# 06-NOTStatusLed.net
KiCad netlist of a schematic drawn in Altium Designer
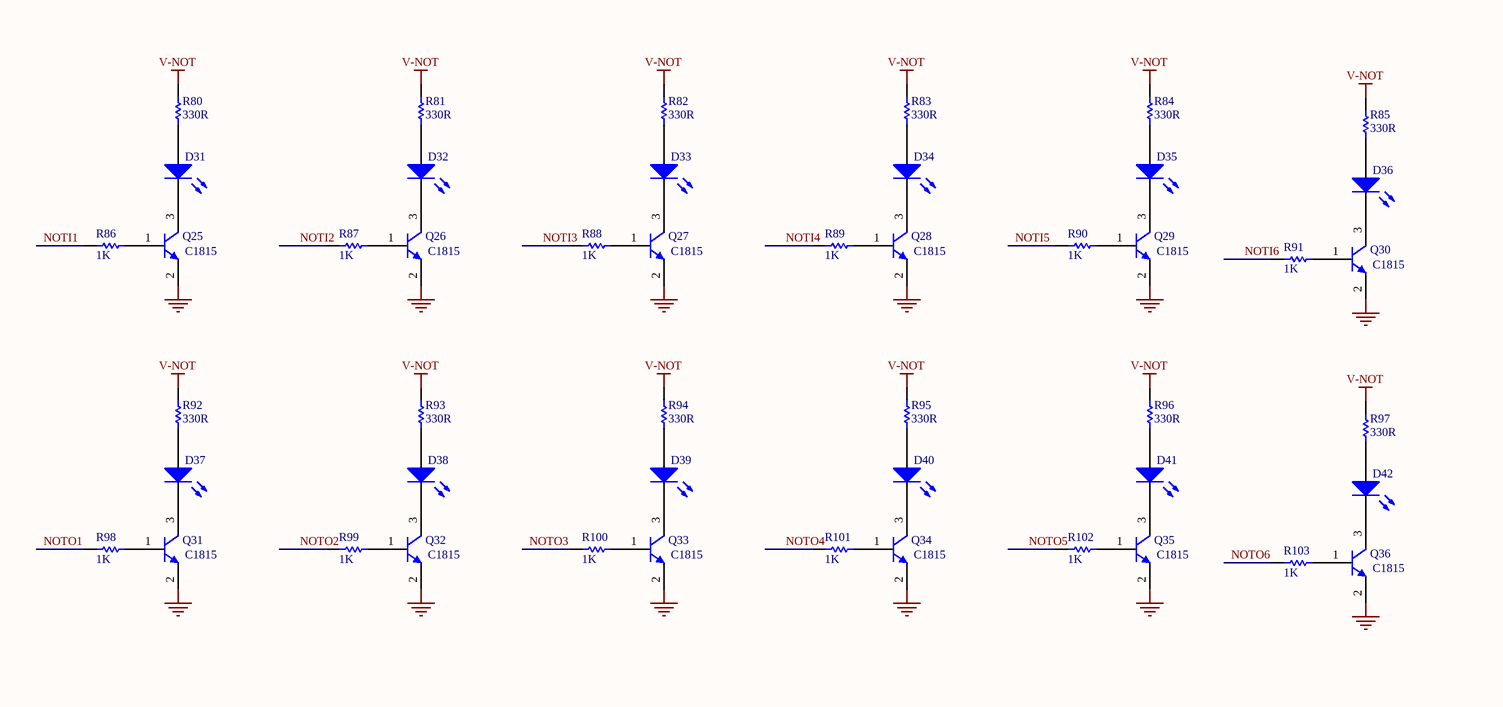
[diagram p0: 06-NOTStatusLed.SchDoc, left]
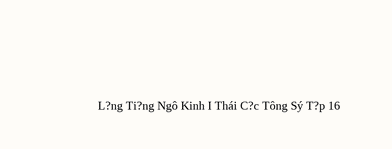
[diagram p1: 06-NOTStatusLed.SchDoc, right]

(export (version "E")
  (design (tool "Eeschema 10.0.6"))
  (components
    (comp (ref "D31")
      (value "LED")
      (footprint "LED-3528")
      (description "Typical RED, GREEN, YELLOW, AMBER GaAs LED")
      (fields (field (name "PUBLISHER") "Altium Limited"))
      (libsource (lib "Miscellaneous Devices") (part "LED2"))
    )
    (comp (ref "D32")
      (value "LED")
      (footprint "LED-3528")
      (description "Typical RED, GREEN, YELLOW, AMBER GaAs LED")
      (fields (field (name "PUBLISHER") "Altium Limited"))
      (libsource (lib "Miscellaneous Devices") (part "LED2"))
    )
    (comp (ref "D33")
      (value "LED")
      (footprint "LED-3528")
      (description "Typical RED, GREEN, YELLOW, AMBER GaAs LED")
      (fields (field (name "PUBLISHER") "Altium Limited"))
      (libsource (lib "Miscellaneous Devices") (part "LED2"))
    )
    (comp (ref "D34")
      (value "LED")
      (footprint "LED-3528")
      (description "Typical RED, GREEN, YELLOW, AMBER GaAs LED")
      (fields (field (name "PUBLISHER") "Altium Limited"))
      (libsource (lib "Miscellaneous Devices") (part "LED2"))
    )
    (comp (ref "D35")
      (value "LED")
      (footprint "LED-3528")
      (description "Typical RED, GREEN, YELLOW, AMBER GaAs LED")
      (fields (field (name "PUBLISHER") "Altium Limited"))
      (libsource (lib "Miscellaneous Devices") (part "LED2"))
    )
    (comp (ref "D36")
      (value "LED")
      (footprint "LED-3528")
      (description "Typical RED, GREEN, YELLOW, AMBER GaAs LED")
      (fields (field (name "PUBLISHER") "Altium Limited"))
      (libsource (lib "Miscellaneous Devices") (part "LED2"))
    )
    (comp (ref "D37")
      (value "LED")
      (footprint "LED-3528")
      (description "Typical RED, GREEN, YELLOW, AMBER GaAs LED")
      (fields (field (name "PUBLISHER") "Altium Limited"))
      (libsource (lib "Miscellaneous Devices") (part "LED2"))
    )
    (comp (ref "D38")
      (value "LED")
      (footprint "LED-3528")
      (description "Typical RED, GREEN, YELLOW, AMBER GaAs LED")
      (fields (field (name "PUBLISHER") "Altium Limited"))
      (libsource (lib "Miscellaneous Devices") (part "LED2"))
    )
    (comp (ref "D39")
      (value "LED")
      (footprint "LED-3528")
      (description "Typical RED, GREEN, YELLOW, AMBER GaAs LED")
      (fields (field (name "PUBLISHER") "Altium Limited"))
      (libsource (lib "Miscellaneous Devices") (part "LED2"))
    )
    (comp (ref "D40")
      (value "LED")
      (footprint "LED-3528")
      (description "Typical RED, GREEN, YELLOW, AMBER GaAs LED")
      (fields (field (name "PUBLISHER") "Altium Limited"))
      (libsource (lib "Miscellaneous Devices") (part "LED2"))
    )
    (comp (ref "D41")
      (value "LED")
      (footprint "LED-3528")
      (description "Typical RED, GREEN, YELLOW, AMBER GaAs LED")
      (fields (field (name "PUBLISHER") "Altium Limited"))
      (libsource (lib "Miscellaneous Devices") (part "LED2"))
    )
    (comp (ref "D42")
      (value "LED")
      (footprint "LED-3528")
      (description "Typical RED, GREEN, YELLOW, AMBER GaAs LED")
      (fields (field (name "PUBLISHER") "Altium Limited"))
      (libsource (lib "Miscellaneous Devices") (part "LED2"))
    )
    (comp (ref "Q25")
      (value "C1815")
      (footprint "SOT23-321")
      (description "NPN Bipolar Transistor")
      (fields (field (name "Comment") "C1815-SMD"))
      (libsource (lib "Miscellaneous Devices") (part "NPN"))
    )
    (comp (ref "Q26")
      (value "C1815")
      (footprint "SOT23-321")
      (description "NPN Bipolar Transistor")
      (fields (field (name "Comment") "C1815-SMD"))
      (libsource (lib "Miscellaneous Devices") (part "NPN"))
    )
    (comp (ref "Q27")
      (value "C1815")
      (footprint "SOT23-321")
      (description "NPN Bipolar Transistor")
      (fields (field (name "Comment") "C1815-SMD"))
      (libsource (lib "Miscellaneous Devices") (part "NPN"))
    )
    (comp (ref "Q28")
      (value "C1815")
      (footprint "SOT23-321")
      (description "NPN Bipolar Transistor")
      (fields (field (name "Comment") "C1815-SMD"))
      (libsource (lib "Miscellaneous Devices") (part "NPN"))
    )
    (comp (ref "Q29")
      (value "C1815")
      (footprint "SOT23-321")
      (description "NPN Bipolar Transistor")
      (fields (field (name "Comment") "C1815-SMD"))
      (libsource (lib "Miscellaneous Devices") (part "NPN"))
    )
    (comp (ref "Q30")
      (value "C1815")
      (footprint "SOT23-321")
      (description "NPN Bipolar Transistor")
      (fields (field (name "Comment") "C1815-SMD"))
      (libsource (lib "Miscellaneous Devices") (part "NPN"))
    )
    (comp (ref "Q31")
      (value "C1815")
      (footprint "SOT23-321")
      (description "NPN Bipolar Transistor")
      (fields (field (name "Comment") "C1815-SMD"))
      (libsource (lib "Miscellaneous Devices") (part "NPN"))
    )
    (comp (ref "Q32")
      (value "C1815")
      (footprint "SOT23-321")
      (description "NPN Bipolar Transistor")
      (fields (field (name "Comment") "C1815-SMD"))
      (libsource (lib "Miscellaneous Devices") (part "NPN"))
    )
    (comp (ref "Q33")
      (value "C1815")
      (footprint "SOT23-321")
      (description "NPN Bipolar Transistor")
      (fields (field (name "Comment") "C1815-SMD"))
      (libsource (lib "Miscellaneous Devices") (part "NPN"))
    )
    (comp (ref "Q34")
      (value "C1815")
      (footprint "SOT23-321")
      (description "NPN Bipolar Transistor")
      (fields (field (name "Comment") "C1815-SMD"))
      (libsource (lib "Miscellaneous Devices") (part "NPN"))
    )
    (comp (ref "Q35")
      (value "C1815")
      (footprint "SOT23-321")
      (description "NPN Bipolar Transistor")
      (fields (field (name "Comment") "C1815-SMD"))
      (libsource (lib "Miscellaneous Devices") (part "NPN"))
    )
    (comp (ref "Q36")
      (value "C1815")
      (footprint "SOT23-321")
      (description "NPN Bipolar Transistor")
      (fields (field (name "Comment") "C1815-SMD"))
      (libsource (lib "Miscellaneous Devices") (part "NPN"))
    )
    (comp (ref "R80")
      (value "330R")
      (footprint "R-0805")
      (description "Resistor")
      (fields (field (name "PUBLISHER") "Altium Limited"))
      (libsource (lib "Miscellaneous Devices") (part "Res1"))
    )
    (comp (ref "R81")
      (value "330R")
      (footprint "R-0805")
      (description "Resistor")
      (fields (field (name "PUBLISHER") "Altium Limited"))
      (libsource (lib "Miscellaneous Devices") (part "Res1"))
    )
    (comp (ref "R82")
      (value "330R")
      (footprint "R-0805")
      (description "Resistor")
      (fields (field (name "PUBLISHER") "Altium Limited"))
      (libsource (lib "Miscellaneous Devices") (part "Res1"))
    )
    (comp (ref "R83")
      (value "330R")
      (footprint "R-0805")
      (description "Resistor")
      (fields (field (name "PUBLISHER") "Altium Limited"))
      (libsource (lib "Miscellaneous Devices") (part "Res1"))
    )
    (comp (ref "R84")
      (value "330R")
      (footprint "R-0805")
      (description "Resistor")
      (fields (field (name "PUBLISHER") "Altium Limited"))
      (libsource (lib "Miscellaneous Devices") (part "Res1"))
    )
    (comp (ref "R85")
      (value "330R")
      (footprint "R-0805")
      (description "Resistor")
      (fields (field (name "PUBLISHER") "Altium Limited"))
      (libsource (lib "Miscellaneous Devices") (part "Res1"))
    )
    (comp (ref "R86")
      (value "1K")
      (footprint "R-0805")
      (description "Resistor")
      (fields (field (name "PUBLISHER") "Altium Limited"))
      (libsource (lib "Miscellaneous Devices") (part "Res1"))
    )
    (comp (ref "R87")
      (value "1K")
      (footprint "R-0805")
      (description "Resistor")
      (fields (field (name "PUBLISHER") "Altium Limited"))
      (libsource (lib "Miscellaneous Devices") (part "Res1"))
    )
    (comp (ref "R88")
      (value "1K")
      (footprint "R-0805")
      (description "Resistor")
      (fields (field (name "PUBLISHER") "Altium Limited"))
      (libsource (lib "Miscellaneous Devices") (part "Res1"))
    )
    (comp (ref "R89")
      (value "1K")
      (footprint "R-0805")
      (description "Resistor")
      (fields (field (name "PUBLISHER") "Altium Limited"))
      (libsource (lib "Miscellaneous Devices") (part "Res1"))
    )
    (comp (ref "R90")
      (value "1K")
      (footprint "R-0805")
      (description "Resistor")
      (fields (field (name "PUBLISHER") "Altium Limited"))
      (libsource (lib "Miscellaneous Devices") (part "Res1"))
    )
    (comp (ref "R91")
      (value "1K")
      (footprint "R-0805")
      (description "Resistor")
      (fields (field (name "PUBLISHER") "Altium Limited"))
      (libsource (lib "Miscellaneous Devices") (part "Res1"))
    )
    (comp (ref "R92")
      (value "330R")
      (footprint "R-0805")
      (description "Resistor")
      (fields (field (name "PUBLISHER") "Altium Limited"))
      (libsource (lib "Miscellaneous Devices") (part "Res1"))
    )
    (comp (ref "R93")
      (value "330R")
      (footprint "R-0805")
      (description "Resistor")
      (fields (field (name "PUBLISHER") "Altium Limited"))
      (libsource (lib "Miscellaneous Devices") (part "Res1"))
    )
    (comp (ref "R94")
      (value "330R")
      (footprint "R-0805")
      (description "Resistor")
      (fields (field (name "PUBLISHER") "Altium Limited"))
      (libsource (lib "Miscellaneous Devices") (part "Res1"))
    )
    (comp (ref "R95")
      (value "330R")
      (footprint "R-0805")
      (description "Resistor")
      (fields (field (name "PUBLISHER") "Altium Limited"))
      (libsource (lib "Miscellaneous Devices") (part "Res1"))
    )
    (comp (ref "R96")
      (value "330R")
      (footprint "R-0805")
      (description "Resistor")
      (fields (field (name "PUBLISHER") "Altium Limited"))
      (libsource (lib "Miscellaneous Devices") (part "Res1"))
    )
    (comp (ref "R97")
      (value "330R")
      (footprint "R-0805")
      (description "Resistor")
      (fields (field (name "PUBLISHER") "Altium Limited"))
      (libsource (lib "Miscellaneous Devices") (part "Res1"))
    )
    (comp (ref "R98")
      (value "1K")
      (footprint "R-0805")
      (description "Resistor")
      (fields (field (name "PUBLISHER") "Altium Limited"))
      (libsource (lib "Miscellaneous Devices") (part "Res1"))
    )
    (comp (ref "R99")
      (value "1K")
      (footprint "R-0805")
      (description "Resistor")
      (fields (field (name "PUBLISHER") "Altium Limited"))
      (libsource (lib "Miscellaneous Devices") (part "Res1"))
    )
    (comp (ref "R100")
      (value "1K")
      (footprint "R-0805")
      (description "Resistor")
      (fields (field (name "PUBLISHER") "Altium Limited"))
      (libsource (lib "Miscellaneous Devices") (part "Res1"))
    )
    (comp (ref "R101")
      (value "1K")
      (footprint "R-0805")
      (description "Resistor")
      (fields (field (name "PUBLISHER") "Altium Limited"))
      (libsource (lib "Miscellaneous Devices") (part "Res1"))
    )
    (comp (ref "R102")
      (value "1K")
      (footprint "R-0805")
      (description "Resistor")
      (fields (field (name "PUBLISHER") "Altium Limited"))
      (libsource (lib "Miscellaneous Devices") (part "Res1"))
    )
    (comp (ref "R103")
      (value "1K")
      (footprint "R-0805")
      (description "Resistor")
      (fields (field (name "PUBLISHER") "Altium Limited"))
      (libsource (lib "Miscellaneous Devices") (part "Res1"))
    )
  )
  (nets
    (net (code "1") (name "/NOTI1") (class "Default")
      (node (ref "R86") (pin "2") (pinfunction "2_2") (pintype "passive"))
    )
    (net (code "2") (name "/NOTI2") (class "Default")
      (node (ref "R87") (pin "2") (pinfunction "2_2") (pintype "passive"))
    )
    (net (code "3") (name "/NOTI3") (class "Default")
      (node (ref "R88") (pin "2") (pinfunction "2_2") (pintype "passive"))
    )
    (net (code "4") (name "/NOTI4") (class "Default")
      (node (ref "R89") (pin "2") (pinfunction "2_2") (pintype "passive"))
    )
    (net (code "5") (name "/NOTI5") (class "Default")
      (node (ref "R90") (pin "2") (pinfunction "2_2") (pintype "passive"))
    )
    (net (code "6") (name "/NOTI6") (class "Default")
      (node (ref "R91") (pin "2") (pinfunction "2_2") (pintype "passive"))
    )
    (net (code "7") (name "/NOTO1") (class "Default")
      (node (ref "R98") (pin "2") (pinfunction "2_2") (pintype "passive"))
    )
    (net (code "8") (name "/NOTO2") (class "Default")
      (node (ref "R99") (pin "2") (pinfunction "2_2") (pintype "passive"))
    )
    (net (code "9") (name "/NOTO3") (class "Default")
      (node (ref "R100") (pin "2") (pinfunction "2_2") (pintype "passive"))
    )
    (net (code "10") (name "/NOTO4") (class "Default")
      (node (ref "R101") (pin "2") (pinfunction "2_2") (pintype "passive"))
    )
    (net (code "11") (name "/NOTO5") (class "Default")
      (node (ref "R102") (pin "2") (pinfunction "2_2") (pintype "passive"))
    )
    (net (code "12") (name "/NOTO6") (class "Default")
      (node (ref "R103") (pin "2") (pinfunction "2_2") (pintype "passive"))
    )
    (net (code "13") (name "GND") (class "Default")
      (node (ref "Q25") (pin "2") (pinfunction "E_2") (pintype "passive"))
      (node (ref "Q26") (pin "2") (pinfunction "E_2") (pintype "passive"))
      (node (ref "Q27") (pin "2") (pinfunction "E_2") (pintype "passive"))
      (node (ref "Q28") (pin "2") (pinfunction "E_2") (pintype "passive"))
      (node (ref "Q29") (pin "2") (pinfunction "E_2") (pintype "passive"))
      (node (ref "Q30") (pin "2") (pinfunction "E_2") (pintype "passive"))
      (node (ref "Q31") (pin "2") (pinfunction "E_2") (pintype "passive"))
      (node (ref "Q32") (pin "2") (pinfunction "E_2") (pintype "passive"))
      (node (ref "Q33") (pin "2") (pinfunction "E_2") (pintype "passive"))
      (node (ref "Q34") (pin "2") (pinfunction "E_2") (pintype "passive"))
      (node (ref "Q35") (pin "2") (pinfunction "E_2") (pintype "passive"))
      (node (ref "Q36") (pin "2") (pinfunction "E_2") (pintype "passive"))
    )
    (net (code "14") (name "Net-(D31-A)") (class "Default")
      (node (ref "D31") (pin "1") (pinfunction "A_1") (pintype "passive"))
      (node (ref "R80") (pin "1") (pinfunction "1_1") (pintype "passive"))
    )
    (net (code "15") (name "Net-(D31-K)") (class "Default")
      (node (ref "D31") (pin "2") (pinfunction "K_2") (pintype "passive"))
      (node (ref "Q25") (pin "3") (pinfunction "C_3") (pintype "passive"))
    )
    (net (code "16") (name "Net-(D32-A)") (class "Default")
      (node (ref "D32") (pin "1") (pinfunction "A_1") (pintype "passive"))
      (node (ref "R81") (pin "1") (pinfunction "1_1") (pintype "passive"))
    )
    (net (code "17") (name "Net-(D32-K)") (class "Default")
      (node (ref "D32") (pin "2") (pinfunction "K_2") (pintype "passive"))
      (node (ref "Q26") (pin "3") (pinfunction "C_3") (pintype "passive"))
    )
    (net (code "18") (name "Net-(D33-A)") (class "Default")
      (node (ref "D33") (pin "1") (pinfunction "A_1") (pintype "passive"))
      (node (ref "R82") (pin "1") (pinfunction "1_1") (pintype "passive"))
    )
    (net (code "19") (name "Net-(D33-K)") (class "Default")
      (node (ref "D33") (pin "2") (pinfunction "K_2") (pintype "passive"))
      (node (ref "Q27") (pin "3") (pinfunction "C_3") (pintype "passive"))
    )
    (net (code "20") (name "Net-(D34-A)") (class "Default")
      (node (ref "D34") (pin "1") (pinfunction "A_1") (pintype "passive"))
      (node (ref "R83") (pin "1") (pinfunction "1_1") (pintype "passive"))
    )
    (net (code "21") (name "Net-(D34-K)") (class "Default")
      (node (ref "D34") (pin "2") (pinfunction "K_2") (pintype "passive"))
      (node (ref "Q28") (pin "3") (pinfunction "C_3") (pintype "passive"))
    )
    (net (code "22") (name "Net-(D35-A)") (class "Default")
      (node (ref "D35") (pin "1") (pinfunction "A_1") (pintype "passive"))
      (node (ref "R84") (pin "1") (pinfunction "1_1") (pintype "passive"))
    )
    (net (code "23") (name "Net-(D35-K)") (class "Default")
      (node (ref "D35") (pin "2") (pinfunction "K_2") (pintype "passive"))
      (node (ref "Q29") (pin "3") (pinfunction "C_3") (pintype "passive"))
    )
    (net (code "24") (name "Net-(D36-A)") (class "Default")
      (node (ref "D36") (pin "1") (pinfunction "A_1") (pintype "passive"))
      (node (ref "R85") (pin "1") (pinfunction "1_1") (pintype "passive"))
    )
    (net (code "25") (name "Net-(D36-K)") (class "Default")
      (node (ref "D36") (pin "2") (pinfunction "K_2") (pintype "passive"))
      (node (ref "Q30") (pin "3") (pinfunction "C_3") (pintype "passive"))
    )
    (net (code "26") (name "Net-(D37-A)") (class "Default")
      (node (ref "D37") (pin "1") (pinfunction "A_1") (pintype "passive"))
      (node (ref "R92") (pin "1") (pinfunction "1_1") (pintype "passive"))
    )
    (net (code "27") (name "Net-(D37-K)") (class "Default")
      (node (ref "D37") (pin "2") (pinfunction "K_2") (pintype "passive"))
      (node (ref "Q31") (pin "3") (pinfunction "C_3") (pintype "passive"))
    )
    (net (code "28") (name "Net-(D38-A)") (class "Default")
      (node (ref "D38") (pin "1") (pinfunction "A_1") (pintype "passive"))
      (node (ref "R93") (pin "1") (pinfunction "1_1") (pintype "passive"))
    )
    (net (code "29") (name "Net-(D38-K)") (class "Default")
      (node (ref "D38") (pin "2") (pinfunction "K_2") (pintype "passive"))
      (node (ref "Q32") (pin "3") (pinfunction "C_3") (pintype "passive"))
    )
    (net (code "30") (name "Net-(D39-A)") (class "Default")
      (node (ref "D39") (pin "1") (pinfunction "A_1") (pintype "passive"))
      (node (ref "R94") (pin "1") (pinfunction "1_1") (pintype "passive"))
    )
    (net (code "31") (name "Net-(D39-K)") (class "Default")
      (node (ref "D39") (pin "2") (pinfunction "K_2") (pintype "passive"))
      (node (ref "Q33") (pin "3") (pinfunction "C_3") (pintype "passive"))
    )
    (net (code "32") (name "Net-(D40-A)") (class "Default")
      (node (ref "D40") (pin "1") (pinfunction "A_1") (pintype "passive"))
      (node (ref "R95") (pin "1") (pinfunction "1_1") (pintype "passive"))
    )
    (net (code "33") (name "Net-(D40-K)") (class "Default")
      (node (ref "D40") (pin "2") (pinfunction "K_2") (pintype "passive"))
      (node (ref "Q34") (pin "3") (pinfunction "C_3") (pintype "passive"))
    )
    (net (code "34") (name "Net-(D41-A)") (class "Default")
      (node (ref "D41") (pin "1") (pinfunction "A_1") (pintype "passive"))
      (node (ref "R96") (pin "1") (pinfunction "1_1") (pintype "passive"))
    )
    (net (code "35") (name "Net-(D41-K)") (class "Default")
      (node (ref "D41") (pin "2") (pinfunction "K_2") (pintype "passive"))
      (node (ref "Q35") (pin "3") (pinfunction "C_3") (pintype "passive"))
    )
    (net (code "36") (name "Net-(D42-A)") (class "Default")
      (node (ref "D42") (pin "1") (pinfunction "A_1") (pintype "passive"))
      (node (ref "R97") (pin "1") (pinfunction "1_1") (pintype "passive"))
    )
    (net (code "37") (name "Net-(D42-K)") (class "Default")
      (node (ref "D42") (pin "2") (pinfunction "K_2") (pintype "passive"))
      (node (ref "Q36") (pin "3") (pinfunction "C_3") (pintype "passive"))
    )
    (net (code "38") (name "Net-(Q25-B)") (class "Default")
      (node (ref "Q25") (pin "1") (pinfunction "B_1") (pintype "passive"))
      (node (ref "R86") (pin "1") (pinfunction "1_1") (pintype "passive"))
    )
    (net (code "39") (name "Net-(Q26-B)") (class "Default")
      (node (ref "Q26") (pin "1") (pinfunction "B_1") (pintype "passive"))
      (node (ref "R87") (pin "1") (pinfunction "1_1") (pintype "passive"))
    )
    (net (code "40") (name "Net-(Q27-B)") (class "Default")
      (node (ref "Q27") (pin "1") (pinfunction "B_1") (pintype "passive"))
      (node (ref "R88") (pin "1") (pinfunction "1_1") (pintype "passive"))
    )
    (net (code "41") (name "Net-(Q28-B)") (class "Default")
      (node (ref "Q28") (pin "1") (pinfunction "B_1") (pintype "passive"))
      (node (ref "R89") (pin "1") (pinfunction "1_1") (pintype "passive"))
    )
    (net (code "42") (name "Net-(Q29-B)") (class "Default")
      (node (ref "Q29") (pin "1") (pinfunction "B_1") (pintype "passive"))
      (node (ref "R90") (pin "1") (pinfunction "1_1") (pintype "passive"))
    )
    (net (code "43") (name "Net-(Q30-B)") (class "Default")
      (node (ref "Q30") (pin "1") (pinfunction "B_1") (pintype "passive"))
      (node (ref "R91") (pin "1") (pinfunction "1_1") (pintype "passive"))
    )
    (net (code "44") (name "Net-(Q31-B)") (class "Default")
      (node (ref "Q31") (pin "1") (pinfunction "B_1") (pintype "passive"))
      (node (ref "R98") (pin "1") (pinfunction "1_1") (pintype "passive"))
    )
    (net (code "45") (name "Net-(Q32-B)") (class "Default")
      (node (ref "Q32") (pin "1") (pinfunction "B_1") (pintype "passive"))
      (node (ref "R99") (pin "1") (pinfunction "1_1") (pintype "passive"))
    )
    (net (code "46") (name "Net-(Q33-B)") (class "Default")
      (node (ref "Q33") (pin "1") (pinfunction "B_1") (pintype "passive"))
      (node (ref "R100") (pin "1") (pinfunction "1_1") (pintype "passive"))
    )
    (net (code "47") (name "Net-(Q34-B)") (class "Default")
      (node (ref "Q34") (pin "1") (pinfunction "B_1") (pintype "passive"))
      (node (ref "R101") (pin "1") (pinfunction "1_1") (pintype "passive"))
    )
    (net (code "48") (name "Net-(Q35-B)") (class "Default")
      (node (ref "Q35") (pin "1") (pinfunction "B_1") (pintype "passive"))
      (node (ref "R102") (pin "1") (pinfunction "1_1") (pintype "passive"))
    )
    (net (code "49") (name "Net-(Q36-B)") (class "Default")
      (node (ref "Q36") (pin "1") (pinfunction "B_1") (pintype "passive"))
      (node (ref "R103") (pin "1") (pinfunction "1_1") (pintype "passive"))
    )
    (net (code "50") (name "V-NOT") (class "Default")
      (node (ref "R80") (pin "2") (pinfunction "2_2") (pintype "passive"))
      (node (ref "R81") (pin "2") (pinfunction "2_2") (pintype "passive"))
      (node (ref "R82") (pin "2") (pinfunction "2_2") (pintype "passive"))
      (node (ref "R83") (pin "2") (pinfunction "2_2") (pintype "passive"))
      (node (ref "R84") (pin "2") (pinfunction "2_2") (pintype "passive"))
      (node (ref "R85") (pin "2") (pinfunction "2_2") (pintype "passive"))
      (node (ref "R92") (pin "2") (pinfunction "2_2") (pintype "passive"))
      (node (ref "R93") (pin "2") (pinfunction "2_2") (pintype "passive"))
      (node (ref "R94") (pin "2") (pinfunction "2_2") (pintype "passive"))
      (node (ref "R95") (pin "2") (pinfunction "2_2") (pintype "passive"))
      (node (ref "R96") (pin "2") (pinfunction "2_2") (pintype "passive"))
      (node (ref "R97") (pin "2") (pinfunction "2_2") (pintype "passive"))
    )
  )
)
